# Top.net
KiCad netlist of a schematic drawn in Altium Designer
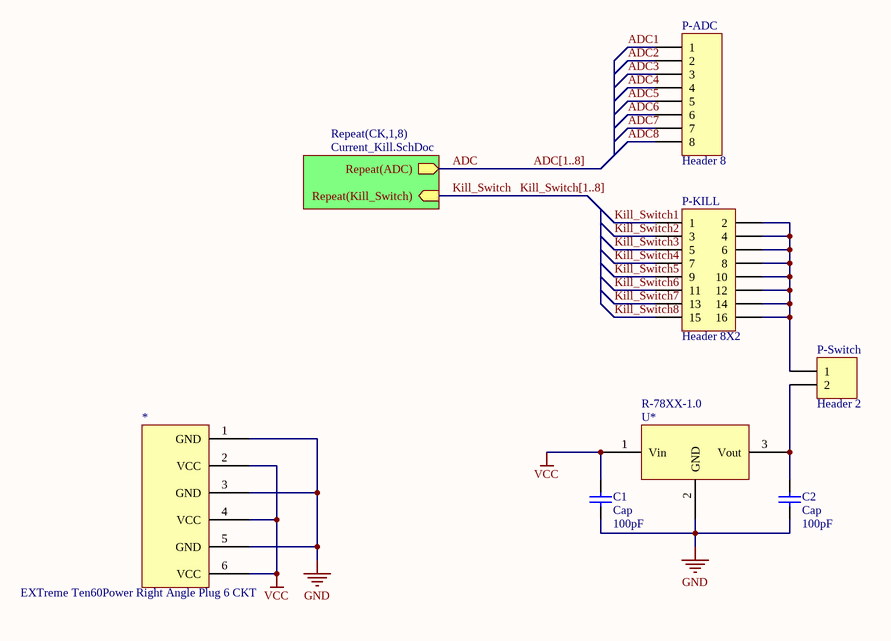
[diagram p0: Top.SchDoc]

(export (version "E")
  (design (tool "Eeschema 10.0.6"))
  (components
    (comp (ref "*")
      (value "EXTreme Ten60Power Right Angle Plug 6 CKT")
      (footprint "EXTreme Ten60Power Right Angle Plug 6 CKT")
      (libsource (lib "Molex_DT") (part "EXTreme Ten60Power Right Angle Plug 6 CKT"))
    )
    (comp (ref "C1")
      (value "Cap")
      (footprint "1608[0603]")
      (description "Capacitor")
      (fields (field (name "ALTIUM_VALUE") "100pF") (field (name "PUBLISHER") "Altium Limited"))
      (libsource (lib "Miscellaneous Devices") (part "Cap"))
    )
    (comp (ref "C2")
      (value "Cap")
      (footprint "1608[0603]")
      (description "Capacitor")
      (fields (field (name "ALTIUM_VALUE") "100pF") (field (name "PUBLISHER") "Altium Limited"))
      (libsource (lib "Miscellaneous Devices") (part "Cap"))
    )
    (comp (ref "P-ADC")
      (value "Header 8")
      (footprint "HDR1X8")
      (description "Header, 8-Pin")
      (fields (field (name "PUBLISHER") "Altium Limited"))
      (libsource (lib "Miscellaneous Connectors") (part "Header 8"))
    )
    (comp (ref "P-KILL")
      (value "Header 8X2")
      (footprint "HDR2X8")
      (description "Header, 8-Pin, Dual row")
      (fields (field (name "PUBLISHER") "Altium Limited"))
      (libsource (lib "Miscellaneous Connectors") (part "Header 8X2"))
    )
    (comp (ref "P-Switch")
      (value "Header 2")
      (footprint "HDR1X2")
      (description "Header, 2-Pin")
      (fields (field (name "PUBLISHER") "Altium Limited"))
      (libsource (lib "Miscellaneous Connectors") (part "Header 2"))
    )
    (comp (ref "U*")
      (value "R-78XX-1.0")
      (footprint "R-785.0-1.0")
      (libsource (lib "RECOM-Reg") (part "R-78XX-1.0"))
    )
  )
  (nets
    (net (code "2") (name "/ADC1") (class "Default")
      (node (ref "P-ADC") (pin "1") (pinfunction "1_1") (pintype "passive"))
    )
    (net (code "3") (name "/ADC2") (class "Default")
      (node (ref "P-ADC") (pin "2") (pinfunction "2_2") (pintype "passive"))
    )
    (net (code "4") (name "/ADC3") (class "Default")
      (node (ref "P-ADC") (pin "3") (pinfunction "3_3") (pintype "passive"))
    )
    (net (code "5") (name "/ADC4") (class "Default")
      (node (ref "P-ADC") (pin "4") (pinfunction "4_4") (pintype "passive"))
    )
    (net (code "6") (name "/ADC5") (class "Default")
      (node (ref "P-ADC") (pin "5") (pinfunction "5_5") (pintype "passive"))
    )
    (net (code "7") (name "/ADC6") (class "Default")
      (node (ref "P-ADC") (pin "6") (pinfunction "6_6") (pintype "passive"))
    )
    (net (code "8") (name "/ADC7") (class "Default")
      (node (ref "P-ADC") (pin "7") (pinfunction "7_7") (pintype "passive"))
    )
    (net (code "9") (name "/ADC8") (class "Default")
      (node (ref "P-ADC") (pin "8") (pinfunction "8_8") (pintype "passive"))
    )
    (net (code "12") (name "/Kill_Switch1") (class "Default")
      (node (ref "P-KILL") (pin "1") (pinfunction "1_1") (pintype "passive"))
    )
    (net (code "13") (name "/Kill_Switch2") (class "Default")
      (node (ref "P-KILL") (pin "3") (pinfunction "3_3") (pintype "passive"))
    )
    (net (code "14") (name "/Kill_Switch3") (class "Default")
      (node (ref "P-KILL") (pin "5") (pinfunction "5_5") (pintype "passive"))
    )
    (net (code "15") (name "/Kill_Switch4") (class "Default")
      (node (ref "P-KILL") (pin "7") (pinfunction "7_7") (pintype "passive"))
    )
    (net (code "16") (name "/Kill_Switch5") (class "Default")
      (node (ref "P-KILL") (pin "9") (pinfunction "9_9") (pintype "passive"))
    )
    (net (code "17") (name "/Kill_Switch6") (class "Default")
      (node (ref "P-KILL") (pin "11") (pinfunction "11_11") (pintype "passive"))
    )
    (net (code "18") (name "/Kill_Switch7") (class "Default")
      (node (ref "P-KILL") (pin "13") (pinfunction "13_13") (pintype "passive"))
    )
    (net (code "19") (name "/Kill_Switch8") (class "Default")
      (node (ref "P-KILL") (pin "15") (pinfunction "15_15") (pintype "passive"))
    )
    (net (code "20") (name "GND") (class "Default")
      (node (ref "*") (pin "1") (pinfunction "GND_1") (pintype "passive"))
      (node (ref "*") (pin "3") (pinfunction "GND_3") (pintype "passive"))
      (node (ref "*") (pin "5") (pinfunction "GND_5") (pintype "passive"))
      (node (ref "C1") (pin "1") (pinfunction "1_1") (pintype "passive"))
      (node (ref "C2") (pin "1") (pinfunction "1_1") (pintype "passive"))
      (node (ref "U*") (pin "2") (pinfunction "GND_2") (pintype "passive"))
    )
    (net (code "21") (name "Net-(P-KILL-Pad10)") (class "Default")
      (node (ref "P-KILL") (pin "10") (pinfunction "10_10") (pintype "passive"))
      (node (ref "P-KILL") (pin "12") (pinfunction "12_12") (pintype "passive"))
      (node (ref "P-KILL") (pin "14") (pinfunction "14_14") (pintype "passive"))
      (node (ref "P-KILL") (pin "16") (pinfunction "16_16") (pintype "passive"))
      (node (ref "P-KILL") (pin "2") (pinfunction "2_2") (pintype "passive"))
      (node (ref "P-KILL") (pin "4") (pinfunction "4_4") (pintype "passive"))
      (node (ref "P-KILL") (pin "6") (pinfunction "6_6") (pintype "passive"))
      (node (ref "P-KILL") (pin "8") (pinfunction "8_8") (pintype "passive"))
      (node (ref "P-Switch") (pin "1") (pinfunction "1_1") (pintype "passive"))
    )
    (net (code "22") (name "Net-(U*-Vout)") (class "Default")
      (node (ref "C2") (pin "2") (pinfunction "2_2") (pintype "passive"))
      (node (ref "P-Switch") (pin "2") (pinfunction "2_2") (pintype "passive"))
      (node (ref "U*") (pin "3") (pinfunction "Vout_3") (pintype "passive"))
    )
    (net (code "23") (name "VCC") (class "Default")
      (node (ref "*") (pin "2") (pinfunction "VCC_2") (pintype "passive"))
      (node (ref "*") (pin "4") (pinfunction "VCC_4") (pintype "passive"))
      (node (ref "*") (pin "6") (pinfunction "VCC_6") (pintype "passive"))
      (node (ref "C1") (pin "2") (pinfunction "2_2") (pintype "passive"))
      (node (ref "U*") (pin "1") (pinfunction "Vin_1") (pintype "passive"))
    )
  )
)
